# justSwitches.net
KiCad netlist of a schematic drawn in EAGLE
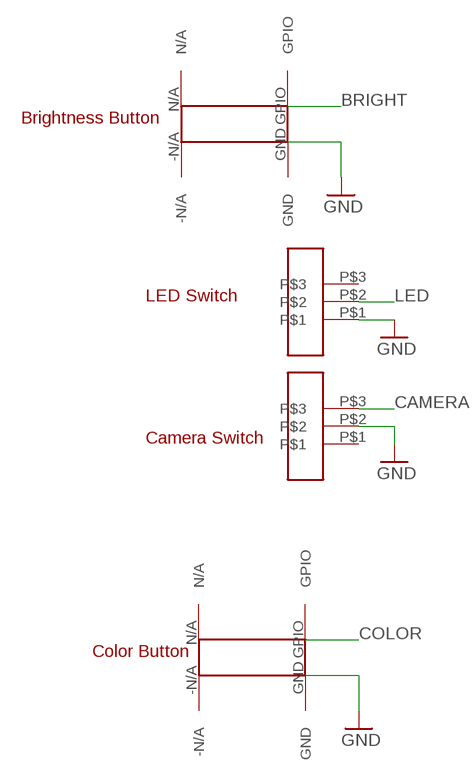
[diagram p0: schematic, sheet 1]

(export (version "E")
  (design (tool "Eeschema 10.0.6"))
  (components
    (comp (ref "U$2")
      (value "G13-SW")
      (footprint "eagle-import:G13-SW")
      (libsource (lib "eagle-import") (part "G13-SW"))
    )
    (comp (ref "U$3")
      (value "G13-SW")
      (footprint "eagle-import:G13-SW")
      (libsource (lib "eagle-import") (part "G13-SW"))
    )
    (comp (ref "U$6")
      (value "G13-BUTTON")
      (footprint "eagle-import:G13-BUTTON")
      (libsource (lib "eagle-import") (part "G13-BUTTON"))
    )
    (comp (ref "U$7")
      (value "G13-BUTTON")
      (footprint "eagle-import:G13-BUTTON")
      (libsource (lib "eagle-import") (part "G13-BUTTON"))
    )
  )
  (nets
    (net (code "1") (name "/BRIGHT") (class "Default")
      (node (ref "U$6") (pin "GPIO") (pinfunction "GPIO_GPIO") (pintype "bidirectional"))
    )
    (net (code "2") (name "/CAMERA") (class "Default")
      (node (ref "U$3") (pin "P$3") (pinfunction "P$3_P$3") (pintype "bidirectional"))
    )
    (net (code "3") (name "/COLOR") (class "Default")
      (node (ref "U$7") (pin "GPIO") (pinfunction "GPIO_GPIO") (pintype "bidirectional"))
    )
    (net (code "4") (name "/LED") (class "Default")
      (node (ref "U$2") (pin "P$2") (pinfunction "P$2_P$2") (pintype "bidirectional"))
    )
    (net (code "5") (name "GND") (class "Default")
      (node (ref "U$2") (pin "P$1") (pinfunction "P$1_P$1") (pintype "bidirectional"))
      (node (ref "U$3") (pin "P$2") (pinfunction "P$2_P$2") (pintype "bidirectional"))
      (node (ref "U$6") (pin "GND") (pinfunction "GND_GND") (pintype "bidirectional"))
      (node (ref "U$7") (pin "GND") (pinfunction "GND_GND") (pintype "bidirectional"))
    )
    (net (code "6") (name "unconnected-(U$2-PadP$3)") (class "Default")
      (node (ref "U$2") (pin "P$3") (pinfunction "P$3_P$3") (pintype "bidirectional"))
    )
    (net (code "7") (name "unconnected-(U$3-PadP$1)") (class "Default")
      (node (ref "U$3") (pin "P$1") (pinfunction "P$1_P$1") (pintype "bidirectional"))
    )
    (net (code "8") (name "unconnected-(U$6-Pad-N{slash}A)") (class "Default")
      (node (ref "U$6") (pin "-N/A") (pinfunction "-N/A_-N/A") (pintype "bidirectional"))
    )
    (net (code "9") (name "unconnected-(U$6-PadN{slash}A)") (class "Default")
      (node (ref "U$6") (pin "N/A") (pinfunction "N/A_N/A") (pintype "bidirectional"))
    )
    (net (code "10") (name "unconnected-(U$7-Pad-N{slash}A)") (class "Default")
      (node (ref "U$7") (pin "-N/A") (pinfunction "-N/A_-N/A") (pintype "bidirectional"))
    )
    (net (code "11") (name "unconnected-(U$7-PadN{slash}A)") (class "Default")
      (node (ref "U$7") (pin "N/A") (pinfunction "N/A_N/A") (pintype "bidirectional"))
    )
  )
)
